# SOIC_TSSOP-20_300mil_DIP.net
KiCad netlist of a schematic drawn in EAGLE
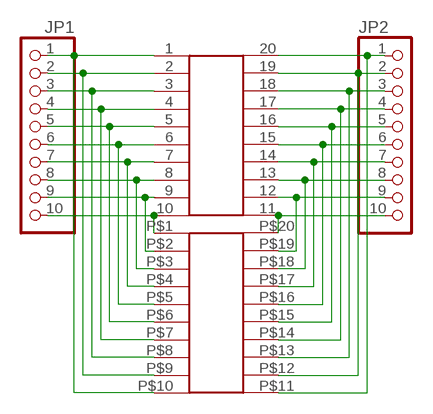
[diagram p0: schematic, sheet 1]

(export (version "E")
  (design (tool "Eeschema 10.0.6"))
  (components
    (comp (ref "JP1")
      (value "PINHD-1X10")
      (footprint "eagle-import:1X10")
      (libsource (lib "eagle-import") (part "PINHD-1X10"))
    )
    (comp (ref "JP2")
      (value "PINHD-1X10")
      (footprint "eagle-import:1X10")
      (libsource (lib "eagle-import") (part "PINHD-1X10"))
    )
    (comp (ref "U$1")
      (value "SMD-20TSSOP")
      (footprint "eagle-import:TSSOP-20NM")
      (libsource (lib "eagle-import") (part "SMD-20TSSOP"))
    )
    (comp (ref "U$2")
      (value "SMD-20SOIC")
      (footprint "eagle-import:SO-20NMW")
      (libsource (lib "eagle-import") (part "SMD-20SOIC"))
    )
  )
  (nets
    (net (code "1") (name "Net-(U$1-P$1)") (class "Default")
      (node (ref "JP1") (pin "1") (pinfunction "1_1") (pintype "passive"))
      (node (ref "U$1") (pin "1") (pinfunction "P$1_1") (pintype "bidirectional"))
      (node (ref "U$2") (pin "P$10") (pinfunction "P$10_P$10") (pintype "bidirectional"))
    )
    (net (code "2") (name "Net-(U$1-P$2)") (class "Default")
      (node (ref "JP1") (pin "2") (pinfunction "2_2") (pintype "passive"))
      (node (ref "U$1") (pin "2") (pinfunction "P$2_2") (pintype "bidirectional"))
      (node (ref "U$2") (pin "P$9") (pinfunction "P$9_P$9") (pintype "bidirectional"))
    )
    (net (code "3") (name "Net-(U$1-P$3)") (class "Default")
      (node (ref "JP1") (pin "3") (pinfunction "3_3") (pintype "passive"))
      (node (ref "U$1") (pin "3") (pinfunction "P$3_3") (pintype "bidirectional"))
      (node (ref "U$2") (pin "P$8") (pinfunction "P$8_P$8") (pintype "bidirectional"))
    )
    (net (code "4") (name "Net-(U$1-P$4)") (class "Default")
      (node (ref "JP1") (pin "4") (pinfunction "4_4") (pintype "passive"))
      (node (ref "U$1") (pin "4") (pinfunction "P$4_4") (pintype "bidirectional"))
      (node (ref "U$2") (pin "P$7") (pinfunction "P$7_P$7") (pintype "bidirectional"))
    )
    (net (code "5") (name "Net-(U$1-P$5)") (class "Default")
      (node (ref "JP1") (pin "5") (pinfunction "5_5") (pintype "passive"))
      (node (ref "U$1") (pin "5") (pinfunction "P$5_5") (pintype "bidirectional"))
      (node (ref "U$2") (pin "P$6") (pinfunction "P$6_P$6") (pintype "bidirectional"))
    )
    (net (code "6") (name "Net-(U$1-P$6)") (class "Default")
      (node (ref "JP1") (pin "6") (pinfunction "6_6") (pintype "passive"))
      (node (ref "U$1") (pin "6") (pinfunction "P$6_6") (pintype "bidirectional"))
      (node (ref "U$2") (pin "P$5") (pinfunction "P$5_P$5") (pintype "bidirectional"))
    )
    (net (code "7") (name "Net-(U$1-P$7)") (class "Default")
      (node (ref "JP1") (pin "7") (pinfunction "7_7") (pintype "passive"))
      (node (ref "U$1") (pin "7") (pinfunction "P$7_7") (pintype "bidirectional"))
      (node (ref "U$2") (pin "P$4") (pinfunction "P$4_P$4") (pintype "bidirectional"))
    )
    (net (code "8") (name "Net-(U$1-P$8)") (class "Default")
      (node (ref "JP1") (pin "8") (pinfunction "8_8") (pintype "passive"))
      (node (ref "U$1") (pin "8") (pinfunction "P$8_8") (pintype "bidirectional"))
      (node (ref "U$2") (pin "P$3") (pinfunction "P$3_P$3") (pintype "bidirectional"))
    )
    (net (code "9") (name "Net-(U$1-P$9)") (class "Default")
      (node (ref "JP1") (pin "9") (pinfunction "9_9") (pintype "passive"))
      (node (ref "U$1") (pin "9") (pinfunction "P$9_9") (pintype "bidirectional"))
      (node (ref "U$2") (pin "P$2") (pinfunction "P$2_P$2") (pintype "bidirectional"))
    )
    (net (code "10") (name "Net-(U$1-P$10)") (class "Default")
      (node (ref "JP1") (pin "10") (pinfunction "10_10") (pintype "passive"))
      (node (ref "U$1") (pin "10") (pinfunction "P$10_10") (pintype "bidirectional"))
      (node (ref "U$2") (pin "P$1") (pinfunction "P$1_P$1") (pintype "bidirectional"))
    )
    (net (code "11") (name "Net-(U$1-P$11)") (class "Default")
      (node (ref "JP2") (pin "10") (pinfunction "10_10") (pintype "passive"))
      (node (ref "U$1") (pin "11") (pinfunction "P$11_11") (pintype "bidirectional"))
      (node (ref "U$2") (pin "P$20") (pinfunction "P$20_P$20") (pintype "bidirectional"))
    )
    (net (code "12") (name "Net-(U$1-P$12)") (class "Default")
      (node (ref "JP2") (pin "9") (pinfunction "9_9") (pintype "passive"))
      (node (ref "U$1") (pin "12") (pinfunction "P$12_12") (pintype "bidirectional"))
      (node (ref "U$2") (pin "P$19") (pinfunction "P$19_P$19") (pintype "bidirectional"))
    )
    (net (code "13") (name "Net-(U$1-P$13)") (class "Default")
      (node (ref "JP2") (pin "8") (pinfunction "8_8") (pintype "passive"))
      (node (ref "U$1") (pin "13") (pinfunction "P$13_13") (pintype "bidirectional"))
      (node (ref "U$2") (pin "P$18") (pinfunction "P$18_P$18") (pintype "bidirectional"))
    )
    (net (code "14") (name "Net-(U$1-P$14)") (class "Default")
      (node (ref "JP2") (pin "7") (pinfunction "7_7") (pintype "passive"))
      (node (ref "U$1") (pin "14") (pinfunction "P$14_14") (pintype "bidirectional"))
      (node (ref "U$2") (pin "P$17") (pinfunction "P$17_P$17") (pintype "bidirectional"))
    )
    (net (code "15") (name "Net-(U$1-P$15)") (class "Default")
      (node (ref "JP2") (pin "6") (pinfunction "6_6") (pintype "passive"))
      (node (ref "U$1") (pin "15") (pinfunction "P$15_15") (pintype "bidirectional"))
      (node (ref "U$2") (pin "P$16") (pinfunction "P$16_P$16") (pintype "bidirectional"))
    )
    (net (code "16") (name "Net-(U$1-P$16)") (class "Default")
      (node (ref "JP2") (pin "5") (pinfunction "5_5") (pintype "passive"))
      (node (ref "U$1") (pin "16") (pinfunction "P$16_16") (pintype "bidirectional"))
      (node (ref "U$2") (pin "P$15") (pinfunction "P$15_P$15") (pintype "bidirectional"))
    )
    (net (code "17") (name "Net-(U$1-P$17)") (class "Default")
      (node (ref "JP2") (pin "4") (pinfunction "4_4") (pintype "passive"))
      (node (ref "U$1") (pin "17") (pinfunction "P$17_17") (pintype "bidirectional"))
      (node (ref "U$2") (pin "P$14") (pinfunction "P$14_P$14") (pintype "bidirectional"))
    )
    (net (code "18") (name "Net-(U$1-P$18)") (class "Default")
      (node (ref "JP2") (pin "3") (pinfunction "3_3") (pintype "passive"))
      (node (ref "U$1") (pin "18") (pinfunction "P$18_18") (pintype "bidirectional"))
      (node (ref "U$2") (pin "P$13") (pinfunction "P$13_P$13") (pintype "bidirectional"))
    )
    (net (code "19") (name "Net-(U$1-P$19)") (class "Default")
      (node (ref "JP2") (pin "2") (pinfunction "2_2") (pintype "passive"))
      (node (ref "U$1") (pin "19") (pinfunction "P$19_19") (pintype "bidirectional"))
      (node (ref "U$2") (pin "P$12") (pinfunction "P$12_P$12") (pintype "bidirectional"))
    )
    (net (code "20") (name "Net-(U$1-P$20)") (class "Default")
      (node (ref "JP2") (pin "1") (pinfunction "1_1") (pintype "passive"))
      (node (ref "U$1") (pin "20") (pinfunction "P$20_20") (pintype "bidirectional"))
      (node (ref "U$2") (pin "P$11") (pinfunction "P$11_P$11") (pintype "bidirectional"))
    )
  )
)
